# precharge.net
KiCad netlist of a schematic drawn in EAGLE
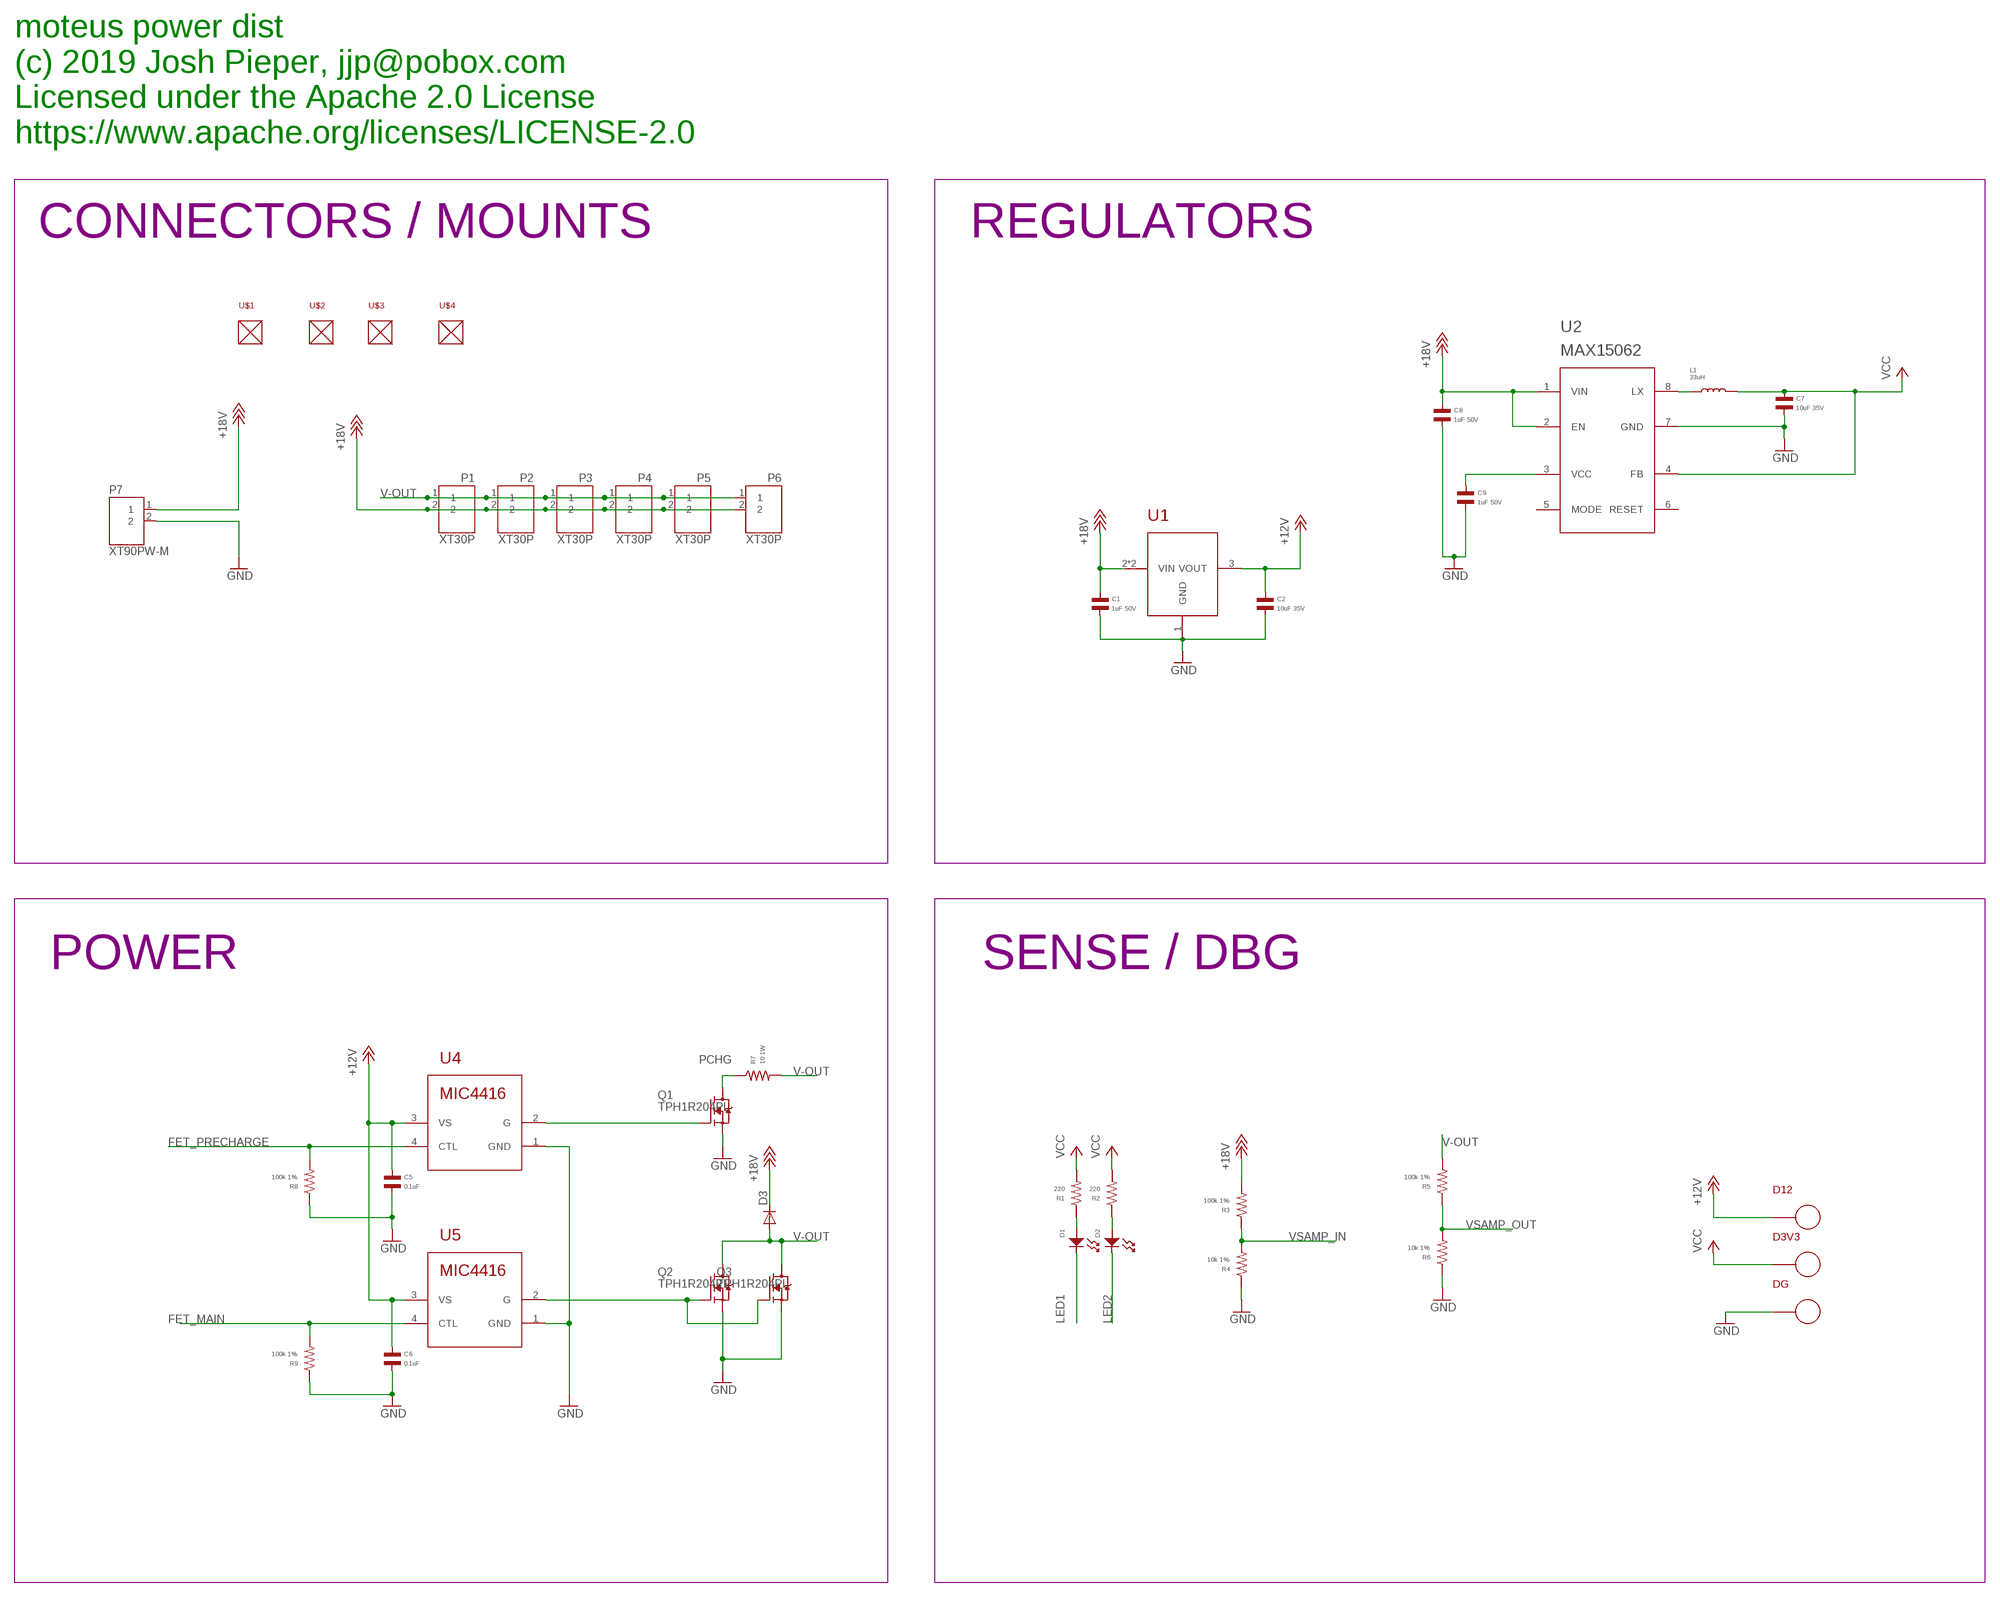
[diagram p0: schematic, sheet 1, part 1 of 2]
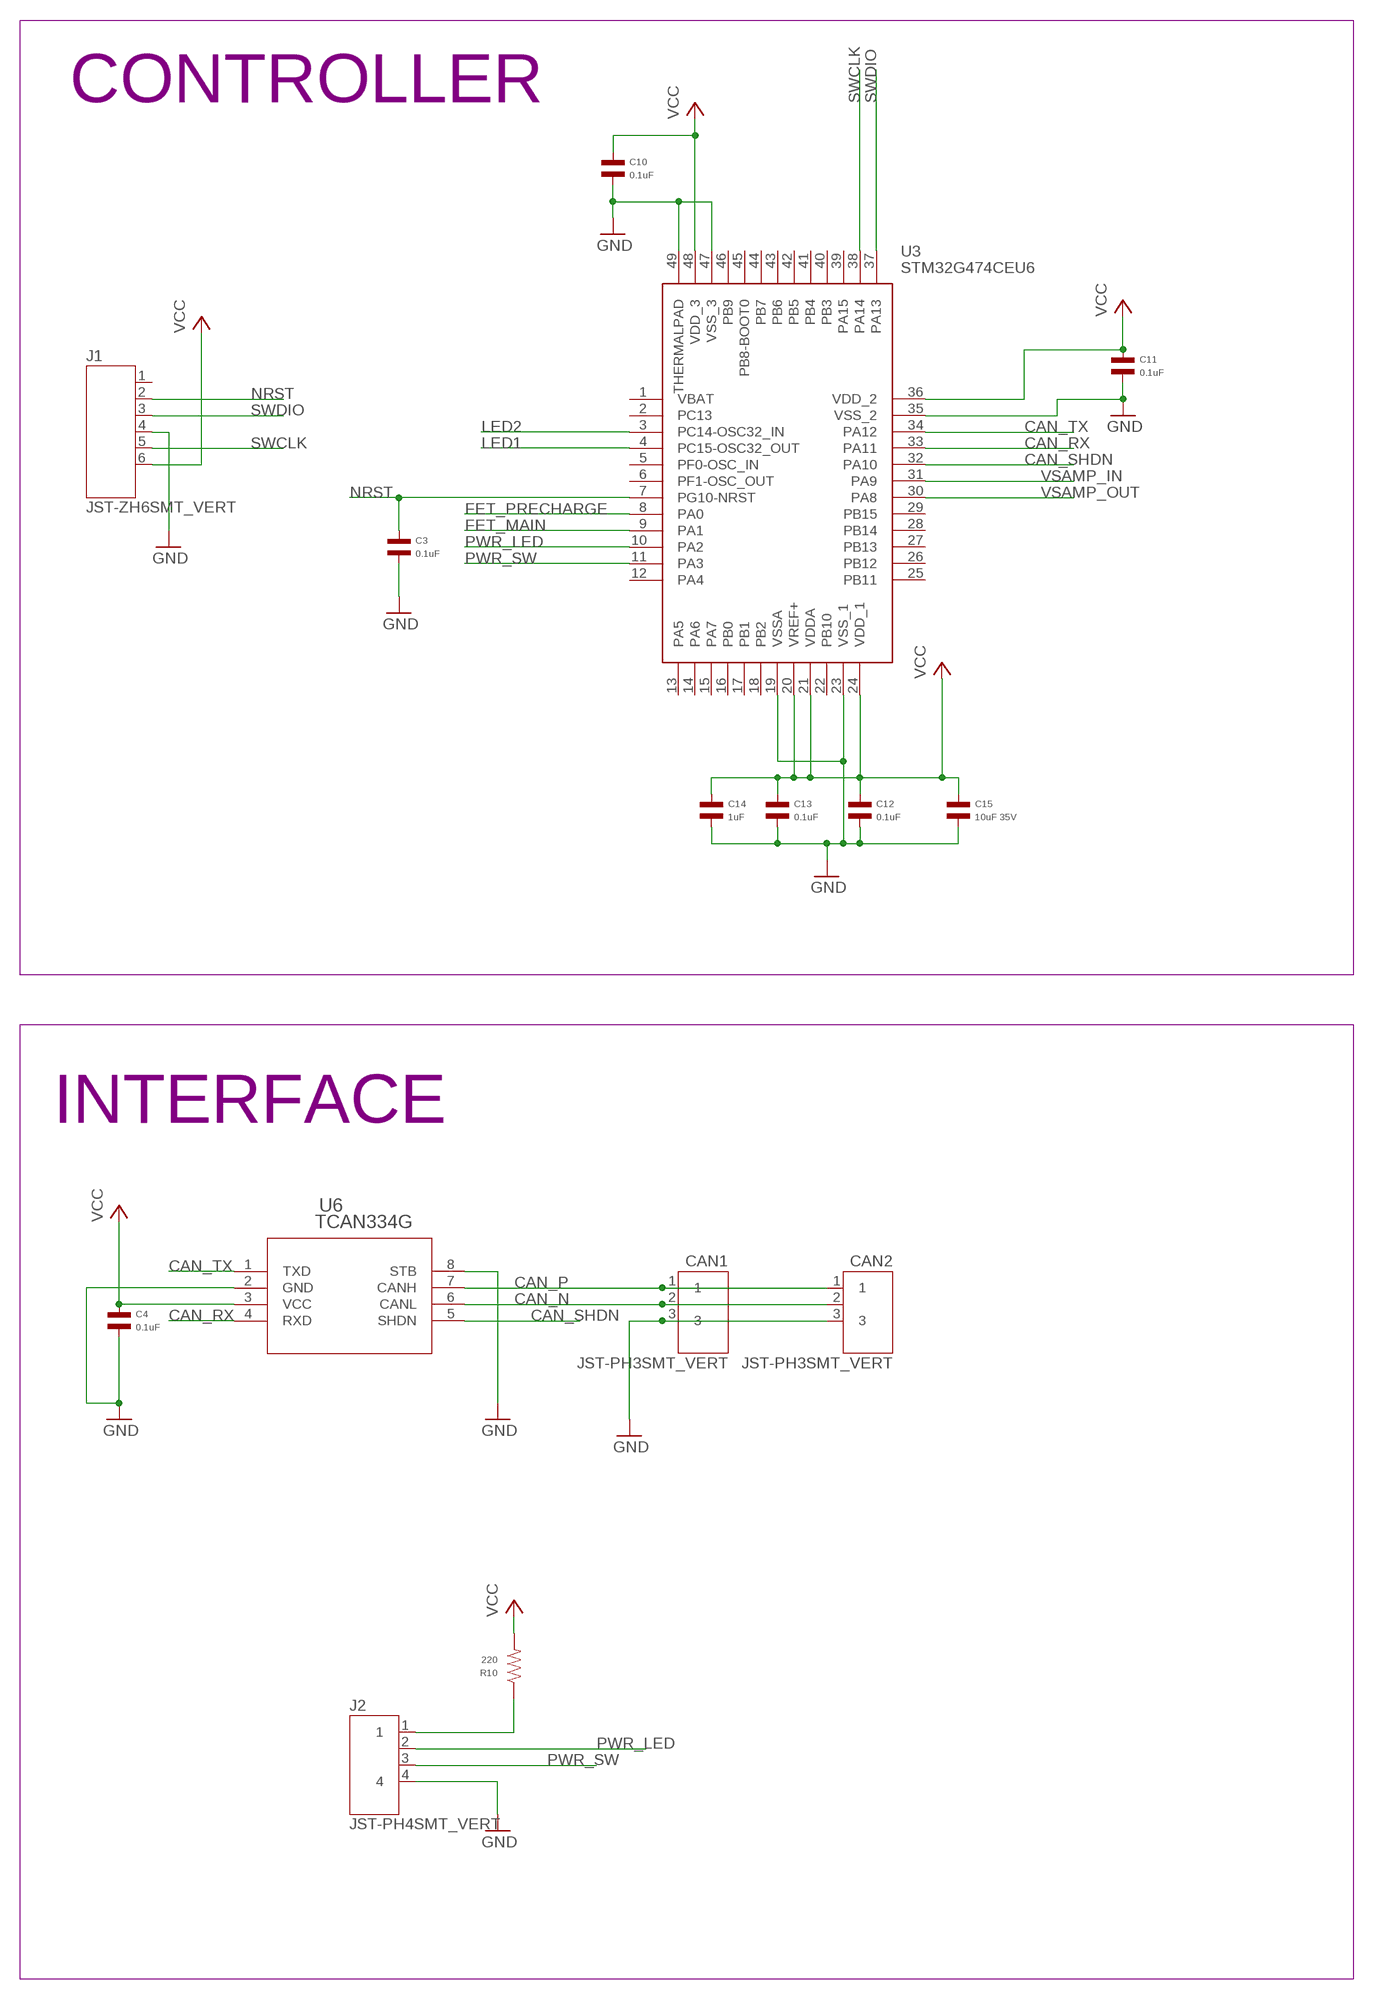
[diagram p1: schematic, sheet 1, part 2 of 2]

(export (version "E")
  (design (tool "Eeschema 10.0.6"))
  (components
    (comp (ref "C1")
      (value "1uF 50V")
      (footprint "eagle-import:C0603")
      (fields (field (name "MF") "SAMSUNG") (field (name "MPN") "CL10A105KB8NNNC"))
      (libsource (lib "eagle-import") (part "CAPACITOR_NP_0603"))
    )
    (comp (ref "C2")
      (value "10uF 35V")
      (footprint "eagle-import:C1206")
      (fields (field (name "MF") "TDK") (field (name "MPN") "CGA5L1X7R1V106K160AC"))
      (libsource (lib "eagle-import") (part "CAPACITOR_NP_1206"))
    )
    (comp (ref "C3")
      (value "0.1uF")
      (footprint "eagle-import:C0402")
      (fields (field (name "HOUSEPART") "1") (field (name "MPN") "MF-CAP-0402-0.1uF"))
      (libsource (lib "eagle-import") (part "CAPACITOR_NP_0402"))
    )
    (comp (ref "C4")
      (value "0.1uF")
      (footprint "eagle-import:C0402")
      (fields (field (name "HOUSEPART") "1") (field (name "MPN") "MF-CAP-0402-0.1uF"))
      (libsource (lib "eagle-import") (part "CAPACITOR_NP_0402"))
    )
    (comp (ref "C5")
      (value "0.1uF")
      (footprint "eagle-import:C0402")
      (fields (field (name "HOUSEPART") "1") (field (name "MPN") "MF-CAP-0402-0.1uF"))
      (libsource (lib "eagle-import") (part "CAPACITOR_NP_0402"))
    )
    (comp (ref "C6")
      (value "0.1uF")
      (footprint "eagle-import:C0402")
      (fields (field (name "HOUSEPART") "1") (field (name "MPN") "MF-CAP-0402-0.1uF"))
      (libsource (lib "eagle-import") (part "CAPACITOR_NP_0402"))
    )
    (comp (ref "C7")
      (value "10uF 35V")
      (footprint "eagle-import:C1206")
      (fields (field (name "MF") "TDK") (field (name "MPN") "CGA5L1X7R1V106K160AC"))
      (libsource (lib "eagle-import") (part "CAPACITOR_NP_1206"))
    )
    (comp (ref "C8")
      (value "1uF 50V")
      (footprint "eagle-import:C0603")
      (fields (field (name "MF") "SAMSUNG") (field (name "MPN") "CL10A105KB8NNNC"))
      (libsource (lib "eagle-import") (part "CAPACITOR_NP_0603"))
    )
    (comp (ref "C9")
      (value "1uF 50V")
      (footprint "eagle-import:C0603")
      (fields (field (name "MF") "SAMSUNG") (field (name "MPN") "CL10A105KB8NNNC"))
      (libsource (lib "eagle-import") (part "CAPACITOR_NP_0603"))
    )
    (comp (ref "C10")
      (value "0.1uF")
      (footprint "eagle-import:C0402")
      (fields (field (name "HOUSEPART") "1") (field (name "MPN") "MF-CAP-0402-0.1uF"))
      (libsource (lib "eagle-import") (part "CAPACITOR_NP_0402"))
    )
    (comp (ref "C11")
      (value "0.1uF")
      (footprint "eagle-import:C0402")
      (fields (field (name "HOUSEPART") "1") (field (name "MPN") "MF-CAP-0402-0.1uF"))
      (libsource (lib "eagle-import") (part "CAPACITOR_NP_0402"))
    )
    (comp (ref "C12")
      (value "0.1uF")
      (footprint "eagle-import:C0402")
      (fields (field (name "HOUSEPART") "1") (field (name "MPN") "MF-CAP-0402-0.1uF"))
      (libsource (lib "eagle-import") (part "CAPACITOR_NP_0402"))
    )
    (comp (ref "C13")
      (value "0.1uF")
      (footprint "eagle-import:C0402")
      (fields (field (name "HOUSEPART") "1") (field (name "MPN") "MF-CAP-0402-0.1uF"))
      (libsource (lib "eagle-import") (part "CAPACITOR_NP_0402"))
    )
    (comp (ref "C14")
      (value "1uF")
      (footprint "eagle-import:C0402")
      (fields (field (name "HOUSEPART") "1") (field (name "MPN") "MF-CAP-0402-1uF"))
      (libsource (lib "eagle-import") (part "CAPACITOR_NP_0402"))
    )
    (comp (ref "C15")
      (value "10uF 35V")
      (footprint "eagle-import:C1206")
      (fields (field (name "MF") "TDK") (field (name "MPN") "CGA5L1X7R1V106K160AC"))
      (libsource (lib "eagle-import") (part "CAPACITOR_NP_1206"))
    )
    (comp (ref "CAN1")
      (value "JST-PH3SMT_VERT")
      (footprint "eagle-import:JST_B3B_PH-SM4-TB(LF)(SN)")
      (fields (field (name "MF") "JST") (field (name "MPN") "B3B-PH-SM4-TB(LF)(SN)"))
      (libsource (lib "eagle-import") (part "JST-PH3SMT_VERT"))
    )
    (comp (ref "CAN2")
      (value "JST-PH3SMT_VERT")
      (footprint "eagle-import:JST_B3B_PH-SM4-TB(LF)(SN)")
      (fields (field (name "MF") "JST") (field (name "MPN") "B3B-PH-SM4-TB(LF)(SN)"))
      (libsource (lib "eagle-import") (part "JST-PH3SMT_VERT"))
    )
    (comp (ref "D1")
      (value "LED_SINGLE-0603")
      (footprint "eagle-import:LED0603")
      (fields
        (field (name "HOUSEPART") "NO")
        (field (name "HOUSEPART_1") "1")
        (field (name "MPN") "MF-LED-0603-RED")
      )
      (libsource (lib "eagle-import") (part "LED_SINGLE-0603"))
    )
    (comp (ref "D2")
      (value "LED_SINGLE-0603")
      (footprint "eagle-import:LED0603")
      (fields
        (field (name "HOUSEPART") "NO")
        (field (name "HOUSEPART_1") "1")
        (field (name "MPN") "MF-LED-0603-RED")
      )
      (libsource (lib "eagle-import") (part "LED_SINGLE-0603"))
    )
    (comp (ref "D3")
      (value "DIODE-")
      (footprint "eagle-import:DO-214AB")
      (fields (field (name "MF") "MICRO COMMERCIAL") (field (name "MPN") "SK510L-TP"))
      (libsource (lib "eagle-import") (part "DIODE-"))
    )
    (comp (ref "D3V3")
      (value "PAD24AWG_PAD")
      (footprint "eagle-import:24AWG_PAD")
      (libsource (lib "eagle-import") (part "PAD24AWG_PAD"))
    )
    (comp (ref "D12")
      (value "PAD24AWG_PAD")
      (footprint "eagle-import:24AWG_PAD")
      (libsource (lib "eagle-import") (part "PAD24AWG_PAD"))
    )
    (comp (ref "DG")
      (value "PAD24AWG_PAD")
      (footprint "eagle-import:24AWG_PAD")
      (libsource (lib "eagle-import") (part "PAD24AWG_PAD"))
    )
    (comp (ref "J1")
      (value "JST-ZH6SMT_VERT")
      (footprint "eagle-import:JST_B6B-ZR-SM4-TF(LF)(SN)")
      (fields (field (name "MF") "JST") (field (name "MPN") "B6B-ZR-SM4-TF(LF)(SN)"))
      (libsource (lib "eagle-import") (part "JST-ZH6SMT_VERT"))
    )
    (comp (ref "J2")
      (value "JST-PH4SMT_VERT")
      (footprint "eagle-import:JST_B4B_PH-SM4-TB(LF)(SN)")
      (fields (field (name "MF") "JST") (field (name "MPN") "B4B-PH-SM4-TB(LF)(SN)"))
      (libsource (lib "eagle-import") (part "JST-PH4SMT_VERT"))
    )
    (comp (ref "L1")
      (value "33uH")
      (footprint "eagle-import:L1210")
      (fields (field (name "MF") "TDK") (field (name "MPN") "NLFV32T-330K-EF") (field (name "POPULATE") "1"))
      (libsource (lib "eagle-import") (part "INDUCTOR_1210"))
    )
    (comp (ref "P1")
      (value "XT30P")
      (footprint "eagle-import:XT30P")
      (libsource (lib "eagle-import") (part "XT30P"))
    )
    (comp (ref "P2")
      (value "XT30P")
      (footprint "eagle-import:XT30P")
      (libsource (lib "eagle-import") (part "XT30P"))
    )
    (comp (ref "P3")
      (value "XT30P")
      (footprint "eagle-import:XT30P")
      (libsource (lib "eagle-import") (part "XT30P"))
    )
    (comp (ref "P4")
      (value "XT30P")
      (footprint "eagle-import:XT30P")
      (libsource (lib "eagle-import") (part "XT30P"))
    )
    (comp (ref "P5")
      (value "XT30P")
      (footprint "eagle-import:XT30P")
      (libsource (lib "eagle-import") (part "XT30P"))
    )
    (comp (ref "P6")
      (value "XT30P")
      (footprint "eagle-import:XT30P")
      (libsource (lib "eagle-import") (part "XT30P"))
    )
    (comp (ref "P7")
      (value "XT90PW-M")
      (footprint "eagle-import:XT90PW-M")
      (libsource (lib "eagle-import") (part "XT90PW-M"))
    )
    (comp (ref "Q1")
      (value "TPH1R204PL")
      (footprint "eagle-import:SOP_ADVANCE")
      (fields (field (name "MF") "Toshiba") (field (name "MPN") "TPH1R204PL,L1Q"))
      (libsource (lib "eagle-import") (part "TPH1R204PL"))
    )
    (comp (ref "Q2")
      (value "TPH1R204PL")
      (footprint "eagle-import:SOP_ADVANCE")
      (fields (field (name "MF") "Toshiba") (field (name "MPN") "TPH1R204PL,L1Q"))
      (libsource (lib "eagle-import") (part "TPH1R204PL"))
    )
    (comp (ref "Q3")
      (value "TPH1R204PL")
      (footprint "eagle-import:SOP_ADVANCE")
      (fields (field (name "MF") "Toshiba") (field (name "MPN") "TPH1R204PL,L1Q"))
      (libsource (lib "eagle-import") (part "TPH1R204PL"))
    )
    (comp (ref "R1")
      (value "220")
      (footprint "eagle-import:R0603")
      (fields (field (name "HOUSEPART") "1") (field (name "MPN") "MF-RES-0603-220"))
      (libsource (lib "eagle-import") (part "RESISTOR_0603"))
    )
    (comp (ref "R2")
      (value "220")
      (footprint "eagle-import:R0603")
      (fields (field (name "HOUSEPART") "1") (field (name "MPN") "MF-RES-0603-220"))
      (libsource (lib "eagle-import") (part "RESISTOR_0603"))
    )
    (comp (ref "R3")
      (value "100k 1%")
      (footprint "eagle-import:R0603")
      (fields (field (name "MF") "VISHAY") (field (name "MPN") "CRCW0603100KFKEA"))
      (libsource (lib "eagle-import") (part "RESISTOR_0603"))
    )
    (comp (ref "R4")
      (value "10k 1%")
      (footprint "eagle-import:R0603")
      (fields (field (name "MF") "PANASONIC") (field (name "MPN") "ERT-J1VG103FA"))
      (libsource (lib "eagle-import") (part "RESISTOR_0603"))
    )
    (comp (ref "R5")
      (value "100k 1%")
      (footprint "eagle-import:R0603")
      (fields (field (name "MF") "VISHAY") (field (name "MPN") "CRCW0603100KFKEA"))
      (libsource (lib "eagle-import") (part "RESISTOR_0603"))
    )
    (comp (ref "R6")
      (value "10k 1%")
      (footprint "eagle-import:R0603")
      (fields (field (name "MF") "PANASONIC") (field (name "MPN") "ERT-J1VG103FA"))
      (libsource (lib "eagle-import") (part "RESISTOR_0603"))
    )
    (comp (ref "R7")
      (value "10 1W")
      (footprint "eagle-import:R1206")
      (fields (field (name "MF") "Susumu") (field (name "MPN") "HRG3216Q-10R0-D-T1"))
      (libsource (lib "eagle-import") (part "RESISTOR_1206"))
    )
    (comp (ref "R8")
      (value "100k 1%")
      (footprint "eagle-import:R0603")
      (fields (field (name "MF") "VISHAY") (field (name "MPN") "CRCW0603100KFKEA"))
      (libsource (lib "eagle-import") (part "RESISTOR_0603"))
    )
    (comp (ref "R9")
      (value "100k 1%")
      (footprint "eagle-import:R0603")
      (fields (field (name "MF") "VISHAY") (field (name "MPN") "CRCW0603100KFKEA"))
      (libsource (lib "eagle-import") (part "RESISTOR_0603"))
    )
    (comp (ref "R10")
      (value "220")
      (footprint "eagle-import:R0603")
      (fields (field (name "HOUSEPART") "1") (field (name "MPN") "MF-RES-0603-220"))
      (libsource (lib "eagle-import") (part "RESISTOR_0603"))
    )
    (comp (ref "U$1")
      (value "MOUNT")
      (footprint "eagle-import:M2.5MOUNT")
      (libsource (lib "eagle-import") (part "MOUNT"))
    )
    (comp (ref "U$2")
      (value "MOUNT")
      (footprint "eagle-import:M2.5MOUNT")
      (libsource (lib "eagle-import") (part "MOUNT"))
    )
    (comp (ref "U$3")
      (value "MOUNT")
      (footprint "eagle-import:M2.5MOUNT")
      (libsource (lib "eagle-import") (part "MOUNT"))
    )
    (comp (ref "U$4")
      (value "MOUNT")
      (footprint "eagle-import:M2.5MOUNT")
      (libsource (lib "eagle-import") (part "MOUNT"))
    )
    (comp (ref "U1")
      (value "ZXTR2012Z")
      (footprint "eagle-import:SOT89")
      (fields (field (name "MF") "DIODES INC") (field (name "MPN") "ZXTR2012Z-13"))
      (libsource (lib "eagle-import") (part "ZXTR2012Z"))
    )
    (comp (ref "U2")
      (value "MAX150628TDFN")
      (footprint "eagle-import:8TDFN")
      (fields (field (name "MF") "MAXIM") (field (name "MPN") "MAX15062AATA+T"))
      (libsource (lib "eagle-import") (part "MAX150628TDFN"))
    )
    (comp (ref "U3")
      (value "STM32G474CEU6")
      (footprint "eagle-import:QFN50P700X700X60-49N")
      (fields (field (name "MOUSER_PART_NUMBER") "511-STM32G474CEU6") (field (name "MF") "ST"))
      (libsource (lib "eagle-import") (part "STM32G474CEU6"))
    )
    (comp (ref "U4")
      (value "MIC4416")
      (footprint "eagle-import:SOT143")
      (fields (field (name "MF") "MICROCHIP") (field (name "MPN") "MIC4416YM4-TR"))
      (libsource (lib "eagle-import") (part "MIC4416"))
    )
    (comp (ref "U5")
      (value "MIC4416")
      (footprint "eagle-import:SOT143")
      (fields (field (name "MF") "MICROCHIP") (field (name "MPN") "MIC4416YM4-TR"))
      (libsource (lib "eagle-import") (part "MIC4416"))
    )
    (comp (ref "U6")
      (value "TCAN334G")
      (footprint "eagle-import:SOT23-8")
      (fields (field (name "MF") "TI") (field (name "MPN") "TCAN334GDR"))
      (libsource (lib "eagle-import") (part "TCAN334G"))
    )
  )
  (nets
    (net (code "1") (name "+12V") (class "Default")
      (node (ref "C2") (pin "P$1") (pinfunction "P$1_P$1") (pintype "passive"))
      (node (ref "C5") (pin "P$1") (pinfunction "P$1_P$1") (pintype "passive"))
      (node (ref "C6") (pin "P$1") (pinfunction "P$1_P$1") (pintype "passive"))
      (node (ref "D12") (pin "P$1") (pinfunction "P$1_P$1") (pintype "bidirectional"))
      (node (ref "U1") (pin "3") (pinfunction "VOUT_3") (pintype "bidirectional"))
      (node (ref "U4") (pin "3") (pinfunction "VS_3") (pintype "bidirectional"))
      (node (ref "U5") (pin "3") (pinfunction "VS_3") (pintype "bidirectional"))
    )
    (net (code "2") (name "+18V") (class "Default")
      (node (ref "C1") (pin "P$1") (pinfunction "P$1_P$1") (pintype "passive"))
      (node (ref "C8") (pin "P$1") (pinfunction "P$1_P$1") (pintype "passive"))
      (node (ref "D3") (pin "C") (pinfunction "C_C") (pintype "passive"))
      (node (ref "P1") (pin "2") (pinfunction "2_2") (pintype "passive"))
      (node (ref "P2") (pin "2") (pinfunction "2_2") (pintype "passive"))
      (node (ref "P3") (pin "2") (pinfunction "2_2") (pintype "passive"))
      (node (ref "P4") (pin "2") (pinfunction "2_2") (pintype "passive"))
      (node (ref "P5") (pin "2") (pinfunction "2_2") (pintype "passive"))
      (node (ref "P6") (pin "2") (pinfunction "2_2") (pintype "passive"))
      (node (ref "P7") (pin "1") (pinfunction "1_1") (pintype "passive"))
      (node (ref "R3") (pin "P$2") (pinfunction "P$2_P$2") (pintype "passive"))
      (node (ref "U1") (pin "2") (pinfunction "VIN_2") (pintype "bidirectional"))
      (node (ref "U1") (pin "PAD") (pinfunction "VIN_PAD") (pintype "bidirectional"))
      (node (ref "U2") (pin "1") (pinfunction "VIN_1") (pintype "passive"))
      (node (ref "U2") (pin "2") (pinfunction "EN_2") (pintype "passive"))
    )
    (net (code "3") (name "/CAN_N") (class "Default")
      (node (ref "CAN1") (pin "2") (pinfunction "2_2") (pintype "passive"))
      (node (ref "CAN2") (pin "2") (pinfunction "2_2") (pintype "passive"))
      (node (ref "U6") (pin "6") (pinfunction "CANL_6") (pintype "bidirectional"))
    )
    (net (code "4") (name "/CAN_P") (class "Default")
      (node (ref "CAN1") (pin "1") (pinfunction "1_1") (pintype "passive"))
      (node (ref "CAN2") (pin "1") (pinfunction "1_1") (pintype "passive"))
      (node (ref "U6") (pin "7") (pinfunction "CANH_7") (pintype "bidirectional"))
    )
    (net (code "5") (name "/CAN_RX") (class "Default")
      (node (ref "U3") (pin "33") (pinfunction "PA11_33") (pintype "bidirectional"))
      (node (ref "U6") (pin "4") (pinfunction "RXD_4") (pintype "output"))
    )
    (net (code "6") (name "/CAN_SHDN") (class "Default")
      (node (ref "U3") (pin "32") (pinfunction "PA10_32") (pintype "bidirectional"))
      (node (ref "U6") (pin "5") (pinfunction "SHDN_5") (pintype "input"))
    )
    (net (code "7") (name "/CAN_TX") (class "Default")
      (node (ref "U3") (pin "34") (pinfunction "PA12_34") (pintype "bidirectional"))
      (node (ref "U6") (pin "1") (pinfunction "TXD_1") (pintype "input"))
    )
    (net (code "8") (name "/FET_MAIN") (class "Default")
      (node (ref "R9") (pin "P$2") (pinfunction "P$2_P$2") (pintype "passive"))
      (node (ref "U3") (pin "9") (pinfunction "PA1_9") (pintype "bidirectional"))
      (node (ref "U5") (pin "4") (pinfunction "CTL_4") (pintype "bidirectional"))
    )
    (net (code "9") (name "/FET_PRECHARGE") (class "Default")
      (node (ref "R8") (pin "P$2") (pinfunction "P$2_P$2") (pintype "passive"))
      (node (ref "U3") (pin "8") (pinfunction "PA0_8") (pintype "bidirectional"))
      (node (ref "U4") (pin "4") (pinfunction "CTL_4") (pintype "bidirectional"))
    )
    (net (code "10") (name "/LED1") (class "Default")
      (node (ref "D1") (pin "CATHODE") (pinfunction "CATHODE_CATHODE") (pintype "power_in"))
      (node (ref "U3") (pin "4") (pinfunction "PC15-OSC32_OUT_4") (pintype "bidirectional"))
    )
    (net (code "11") (name "/LED2") (class "Default")
      (node (ref "D2") (pin "CATHODE") (pinfunction "CATHODE_CATHODE") (pintype "power_in"))
      (node (ref "U3") (pin "3") (pinfunction "PC14-OSC32_IN_3") (pintype "bidirectional"))
    )
    (net (code "12") (name "/NRST") (class "Default")
      (node (ref "C3") (pin "P$1") (pinfunction "P$1_P$1") (pintype "passive"))
      (node (ref "J1") (pin "2") (pinfunction "2_2") (pintype "passive"))
      (node (ref "U3") (pin "7") (pinfunction "PG10-NRST_7") (pintype "bidirectional"))
    )
    (net (code "13") (name "/PCHG") (class "Default")
      (node (ref "Q1") (pin "5") (pinfunction "D_5") (pintype "passive"))
      (node (ref "Q1") (pin "6") (pinfunction "D_6") (pintype "passive"))
      (node (ref "Q1") (pin "7") (pinfunction "D_7") (pintype "passive"))
      (node (ref "Q1") (pin "8") (pinfunction "D_8") (pintype "passive"))
      (node (ref "Q1") (pin "PAD") (pinfunction "D_PAD") (pintype "passive"))
      (node (ref "R7") (pin "P$1") (pinfunction "P$1_P$1") (pintype "passive"))
    )
    (net (code "14") (name "/PWR_LED") (class "Default")
      (node (ref "J2") (pin "2") (pinfunction "2_2") (pintype "passive"))
      (node (ref "U3") (pin "10") (pinfunction "PA2_10") (pintype "bidirectional"))
    )
    (net (code "15") (name "/PWR_SW") (class "Default")
      (node (ref "J2") (pin "3") (pinfunction "3_3") (pintype "passive"))
      (node (ref "U3") (pin "11") (pinfunction "PA3_11") (pintype "bidirectional"))
    )
    (net (code "16") (name "/SWCLK") (class "Default")
      (node (ref "J1") (pin "5") (pinfunction "5_5") (pintype "passive"))
      (node (ref "U3") (pin "38") (pinfunction "PA14_38") (pintype "bidirectional"))
    )
    (net (code "17") (name "/SWDIO") (class "Default")
      (node (ref "J1") (pin "3") (pinfunction "3_3") (pintype "passive"))
      (node (ref "U3") (pin "37") (pinfunction "PA13_37") (pintype "bidirectional"))
    )
    (net (code "18") (name "/V-OUT") (class "Default")
      (node (ref "D3") (pin "A") (pinfunction "A_A") (pintype "passive"))
      (node (ref "P1") (pin "1") (pinfunction "1_1") (pintype "passive"))
      (node (ref "P2") (pin "1") (pinfunction "1_1") (pintype "passive"))
      (node (ref "P3") (pin "1") (pinfunction "1_1") (pintype "passive"))
      (node (ref "P4") (pin "1") (pinfunction "1_1") (pintype "passive"))
      (node (ref "P5") (pin "1") (pinfunction "1_1") (pintype "passive"))
      (node (ref "P6") (pin "1") (pinfunction "1_1") (pintype "passive"))
      (node (ref "Q2") (pin "5") (pinfunction "D_5") (pintype "passive"))
      (node (ref "Q2") (pin "6") (pinfunction "D_6") (pintype "passive"))
      (node (ref "Q2") (pin "7") (pinfunction "D_7") (pintype "passive"))
      (node (ref "Q2") (pin "8") (pinfunction "D_8") (pintype "passive"))
      (node (ref "Q2") (pin "PAD") (pinfunction "D_PAD") (pintype "passive"))
      (node (ref "Q3") (pin "5") (pinfunction "D_5") (pintype "passive"))
      (node (ref "Q3") (pin "6") (pinfunction "D_6") (pintype "passive"))
      (node (ref "Q3") (pin "7") (pinfunction "D_7") (pintype "passive"))
      (node (ref "Q3") (pin "8") (pinfunction "D_8") (pintype "passive"))
      (node (ref "Q3") (pin "PAD") (pinfunction "D_PAD") (pintype "passive"))
      (node (ref "R5") (pin "P$2") (pinfunction "P$2_P$2") (pintype "passive"))
      (node (ref "R7") (pin "P$2") (pinfunction "P$2_P$2") (pintype "passive"))
    )
    (net (code "19") (name "/VSAMP_IN") (class "Default")
      (node (ref "R3") (pin "P$1") (pinfunction "P$1_P$1") (pintype "passive"))
      (node (ref "R4") (pin "P$2") (pinfunction "P$2_P$2") (pintype "passive"))
      (node (ref "U3") (pin "31") (pinfunction "PA9_31") (pintype "bidirectional"))
    )
    (net (code "20") (name "/VSAMP_OUT") (class "Default")
      (node (ref "R5") (pin "P$1") (pinfunction "P$1_P$1") (pintype "passive"))
      (node (ref "R6") (pin "P$2") (pinfunction "P$2_P$2") (pintype "passive"))
      (node (ref "U3") (pin "30") (pinfunction "PA8_30") (pintype "bidirectional"))
    )
    (net (code "21") (name "GND") (class "Default")
      (node (ref "C1") (pin "P$2") (pinfunction "P$2_P$2") (pintype "passive"))
      (node (ref "C10") (pin "P$2") (pinfunction "P$2_P$2") (pintype "passive"))
      (node (ref "C11") (pin "P$2") (pinfunction "P$2_P$2") (pintype "passive"))
      (node (ref "C12") (pin "P$2") (pinfunction "P$2_P$2") (pintype "passive"))
      (node (ref "C13") (pin "P$2") (pinfunction "P$2_P$2") (pintype "passive"))
      (node (ref "C14") (pin "P$2") (pinfunction "P$2_P$2") (pintype "passive"))
      (node (ref "C15") (pin "P$2") (pinfunction "P$2_P$2") (pintype "passive"))
      (node (ref "C2") (pin "P$2") (pinfunction "P$2_P$2") (pintype "passive"))
      (node (ref "C3") (pin "P$2") (pinfunction "P$2_P$2") (pintype "passive"))
      (node (ref "C4") (pin "P$2") (pinfunction "P$2_P$2") (pintype "passive"))
      (node (ref "C5") (pin "P$2") (pinfunction "P$2_P$2") (pintype "passive"))
      (node (ref "C6") (pin "P$2") (pinfunction "P$2_P$2") (pintype "passive"))
      (node (ref "C7") (pin "P$2") (pinfunction "P$2_P$2") (pintype "passive"))
      (node (ref "C8") (pin "P$2") (pinfunction "P$2_P$2") (pintype "passive"))
      (node (ref "C9") (pin "P$2") (pinfunction "P$2_P$2") (pintype "passive"))
      (node (ref "CAN1") (pin "3") (pinfunction "3_3") (pintype "passive"))
      (node (ref "CAN2") (pin "3") (pinfunction "3_3") (pintype "passive"))
      (node (ref "DG") (pin "P$1") (pinfunction "P$1_P$1") (pintype "bidirectional"))
      (node (ref "J1") (pin "4") (pinfunction "4_4") (pintype "passive"))
      (node (ref "J2") (pin "4") (pinfunction "4_4") (pintype "passive"))
      (node (ref "P7") (pin "2") (pinfunction "2_2") (pintype "passive"))
      (node (ref "Q1") (pin "1") (pinfunction "S_1") (pintype "passive"))
      (node (ref "Q1") (pin "2") (pinfunction "S_2") (pintype "passive"))
      (node (ref "Q1") (pin "3") (pinfunction "S_3") (pintype "passive"))
      (node (ref "Q2") (pin "1") (pinfunction "S_1") (pintype "passive"))
      (node (ref "Q2") (pin "2") (pinfunction "S_2") (pintype "passive"))
      (node (ref "Q2") (pin "3") (pinfunction "S_3") (pintype "passive"))
      (node (ref "Q3") (pin "1") (pinfunction "S_1") (pintype "passive"))
      (node (ref "Q3") (pin "2") (pinfunction "S_2") (pintype "passive"))
      (node (ref "Q3") (pin "3") (pinfunction "S_3") (pintype "passive"))
      (node (ref "R4") (pin "P$1") (pinfunction "P$1_P$1") (pintype "passive"))
      (node (ref "R6") (pin "P$1") (pinfunction "P$1_P$1") (pintype "passive"))
      (node (ref "R8") (pin "P$1") (pinfunction "P$1_P$1") (pintype "passive"))
      (node (ref "R9") (pin "P$1") (pinfunction "P$1_P$1") (pintype "passive"))
      (node (ref "U1") (pin "1") (pinfunction "GND_1") (pintype "bidirectional"))
      (node (ref "U2") (pin "7") (pinfunction "GND_7") (pintype "passive"))
      (node (ref "U3") (pin "19") (pinfunction "VSSA_19") (pintype "bidirectional"))
      (node (ref "U3") (pin "23") (pinfunction "VSS_1_23") (pintype "bidirectional"))
      (node (ref "U3") (pin "35") (pinfunction "VSS_2_35") (pintype "bidirectional"))
      (node (ref "U3") (pin "47") (pinfunction "VSS_3_47") (pintype "bidirectional"))
      (node (ref "U3") (pin "49") (pinfunction "THERMALPAD_49") (pintype "bidirectional"))
      (node (ref "U4") (pin "1") (pinfunction "GND_1") (pintype "bidirectional"))
      (node (ref "U5") (pin "1") (pinfunction "GND_1") (pintype "bidirectional"))
      (node (ref "U6") (pin "2") (pinfunction "GND_2") (pintype "power_in"))
      (node (ref "U6") (pin "8") (pinfunction "STB_8") (pintype "input"))
    )
    (net (code "22") (name "Net-(D1-PadANODE)") (class "Default")
      (node (ref "D1") (pin "ANODE") (pinfunction "ANODE_ANODE") (pintype "power_in"))
      (node (ref "R1") (pin "P$1") (pinfunction "P$1_P$1") (pintype "passive"))
    )
    (net (code "23") (name "Net-(D2-PadANODE)") (class "Default")
      (node (ref "D2") (pin "ANODE") (pinfunction "ANODE_ANODE") (pintype "power_in"))
      (node (ref "R2") (pin "P$1") (pinfunction "P$1_P$1") (pintype "passive"))
    )
    (net (code "24") (name "Net-(J2-Pad1)") (class "Default")
      (node (ref "J2") (pin "1") (pinfunction "1_1") (pintype "passive"))
      (node (ref "R10") (pin "P$1") (pinfunction "P$1_P$1") (pintype "passive"))
    )
    (net (code "25") (name "Net-(Q1-G)") (class "Default")
      (node (ref "Q1") (pin "4") (pinfunction "G_4") (pintype "passive"))
      (node (ref "U4") (pin "2") (pinfunction "G_2") (pintype "bidirectional"))
    )
    (net (code "26") (name "Net-(Q2-G)") (class "Default")
      (node (ref "Q2") (pin "4") (pinfunction "G_4") (pintype "passive"))
      (node (ref "Q3") (pin "4") (pinfunction "G_4") (pintype "passive"))
      (node (ref "U5") (pin "2") (pinfunction "G_2") (pintype "bidirectional"))
    )
    (net (code "27") (name "Net-(U2-LX)") (class "Default")
      (node (ref "L1") (pin "P$1") (pinfunction "P$1_P$1") (pintype "passive"))
      (node (ref "U2") (pin "8") (pinfunction "LX_8") (pintype "passive"))
    )
    (net (code "28") (name "Net-(U2-VCC)") (class "Default")
      (node (ref "C9") (pin "P$1") (pinfunction "P$1_P$1") (pintype "passive"))
      (node (ref "U2") (pin "3") (pinfunction "VCC_3") (pintype "passive"))
    )
    (net (code "29") (name "VCC") (class "Default")
      (node (ref "C10") (pin "P$1") (pinfunction "P$1_P$1") (pintype "passive"))
      (node (ref "C11") (pin "P$1") (pinfunction "P$1_P$1") (pintype "passive"))
      (node (ref "C12") (pin "P$1") (pinfunction "P$1_P$1") (pintype "passive"))
      (node (ref "C13") (pin "P$1") (pinfunction "P$1_P$1") (pintype "passive"))
      (node (ref "C14") (pin "P$1") (pinfunction "P$1_P$1") (pintype "passive"))
      (node (ref "C15") (pin "P$1") (pinfunction "P$1_P$1") (pintype "passive"))
      (node (ref "C4") (pin "P$1") (pinfunction "P$1_P$1") (pintype "passive"))
      (node (ref "C7") (pin "P$1") (pinfunction "P$1_P$1") (pintype "passive"))
      (node (ref "D3V3") (pin "P$1") (pinfunction "P$1_P$1") (pintype "bidirectional"))
      (node (ref "J1") (pin "6") (pinfunction "6_6") (pintype "passive"))
      (node (ref "L1") (pin "P$2") (pinfunction "P$2_P$2") (pintype "passive"))
      (node (ref "R1") (pin "P$2") (pinfunction "P$2_P$2") (pintype "passive"))
      (node (ref "R10") (pin "P$2") (pinfunction "P$2_P$2") (pintype "passive"))
      (node (ref "R2") (pin "P$2") (pinfunction "P$2_P$2") (pintype "passive"))
      (node (ref "U2") (pin "4") (pinfunction "FB_4") (pintype "passive"))
      (node (ref "U3") (pin "20") (pinfunction "VREF+_20") (pintype "bidirectional"))
      (node (ref "U3") (pin "21") (pinfunction "VDDA_21") (pintype "bidirectional"))
      (node (ref "U3") (pin "24") (pinfunction "VDD_1_24") (pintype "bidirectional"))
      (node (ref "U3") (pin "36") (pinfunction "VDD_2_36") (pintype "bidirectional"))
      (node (ref "U3") (pin "48") (pinfunction "VDD_3_48") (pintype "bidirectional"))
      (node (ref "U6") (pin "3") (pinfunction "VCC_3") (pintype "power_in"))
    )
    (net (code "30") (name "unconnected-(J1-Pad1)") (class "Default")
      (node (ref "J1") (pin "1") (pinfunction "1_1") (pintype "passive"))
    )
    (net (code "31") (name "unconnected-(U2-MODE-Pad5)") (class "Default")
      (node (ref "U2") (pin "5") (pinfunction "MODE_5") (pintype "passive"))
    )
    (net (code "32") (name "unconnected-(U2-RESET-Pad6)") (class "Default")
      (node (ref "U2") (pin "6") (pinfunction "RESET_6") (pintype "passive"))
    )
    (net (code "33") (name "unconnected-(U3-PA4-Pad12)") (class "Default")
      (node (ref "U3") (pin "12") (pinfunction "PA4_12") (pintype "bidirectional"))
    )
    (net (code "34") (name "unconnected-(U3-PA5-Pad13)") (class "Default")
      (node (ref "U3") (pin "13") (pinfunction "PA5_13") (pintype "bidirectional"))
    )
    (net (code "35") (name "unconnected-(U3-PA6-Pad14)") (class "Default")
      (node (ref "U3") (pin "14") (pinfunction "PA6_14") (pintype "bidirectional"))
    )
    (net (code "36") (name "unconnected-(U3-PA7-Pad15)") (class "Default")
      (node (ref "U3") (pin "15") (pinfunction "PA7_15") (pintype "bidirectional"))
    )
    (net (code "37") (name "unconnected-(U3-PA15-Pad39)") (class "Default")
      (node (ref "U3") (pin "39") (pinfunction "PA15_39") (pintype "bidirectional"))
    )
    (net (code "38") (name "unconnected-(U3-PB0-Pad16)") (class "Default")
      (node (ref "U3") (pin "16") (pinfunction "PB0_16") (pintype "bidirectional"))
    )
    (net (code "39") (name "unconnected-(U3-PB1-Pad17)") (class "Default")
      (node (ref "U3") (pin "17") (pinfunction "PB1_17") (pintype "bidirectional"))
    )
    (net (code "40") (name "unconnected-(U3-PB2-Pad18)") (class "Default")
      (node (ref "U3") (pin "18") (pinfunction "PB2_18") (pintype "bidirectional"))
    )
    (net (code "41") (name "unconnected-(U3-PB3-Pad40)") (class "Default")
      (node (ref "U3") (pin "40") (pinfunction "PB3_40") (pintype "bidirectional"))
    )
    (net (code "42") (name "unconnected-(U3-PB4-Pad41)") (class "Default")
      (node (ref "U3") (pin "41") (pinfunction "PB4_41") (pintype "bidirectional"))
    )
    (net (code "43") (name "unconnected-(U3-PB5-Pad42)") (class "Default")
      (node (ref "U3") (pin "42") (pinfunction "PB5_42") (pintype "bidirectional"))
    )
    (net (code "44") (name "unconnected-(U3-PB6-Pad43)") (class "Default")
      (node (ref "U3") (pin "43") (pinfunction "PB6_43") (pintype "bidirectional"))
    )
    (net (code "45") (name "unconnected-(U3-PB7-Pad44)") (class "Default")
      (node (ref "U3") (pin "44") (pinfunction "PB7_44") (pintype "bidirectional"))
    )
    (net (code "46") (name "unconnected-(U3-PB8-BOOT0-Pad45)") (class "Default")
      (node (ref "U3") (pin "45") (pinfunction "PB8-BOOT0_45") (pintype "bidirectional"))
    )
    (net (code "47") (name "unconnected-(U3-PB9-Pad46)") (class "Default")
      (node (ref "U3") (pin "46") (pinfunction "PB9_46") (pintype "bidirectional"))
    )
    (net (code "48") (name "unconnected-(U3-PB10-Pad22)") (class "Default")
      (node (ref "U3") (pin "22") (pinfunction "PB10_22") (pintype "bidirectional"))
    )
    (net (code "49") (name "unconnected-(U3-PB11-Pad25)") (class "Default")
      (node (ref "U3") (pin "25") (pinfunction "PB11_25") (pintype "bidirectional"))
    )
    (net (code "50") (name "unconnected-(U3-PB12-Pad26)") (class "Default")
      (node (ref "U3") (pin "26") (pinfunction "PB12_26") (pintype "bidirectional"))
    )
    (net (code "51") (name "unconnected-(U3-PB13-Pad27)") (class "Default")
      (node (ref "U3") (pin "27") (pinfunction "PB13_27") (pintype "bidirectional"))
    )
    (net (code "52") (name "unconnected-(U3-PB14-Pad28)") (class "Default")
      (node (ref "U3") (pin "28") (pinfunction "PB14_28") (pintype "bidirectional"))
    )
    (net (code "53") (name "unconnected-(U3-PB15-Pad29)") (class "Default")
      (node (ref "U3") (pin "29") (pinfunction "PB15_29") (pintype "bidirectional"))
    )
    (net (code "54") (name "unconnected-(U3-PC13-Pad2)") (class "Default")
      (node (ref "U3") (pin "2") (pinfunction "PC13_2") (pintype "bidirectional"))
    )
    (net (code "55") (name "unconnected-(U3-PF0-OSC_IN-Pad5)") (class "Default")
      (node (ref "U3") (pin "5") (pinfunction "PF0-OSC_IN_5") (pintype "bidirectional"))
    )
    (net (code "56") (name "unconnected-(U3-PF1-OSC_OUT-Pad6)") (class "Default")
      (node (ref "U3") (pin "6") (pinfunction "PF1-OSC_OUT_6") (pintype "bidirectional"))
    )
    (net (code "57") (name "unconnected-(U3-VBAT-Pad1)") (class "Default")
      (node (ref "U3") (pin "1") (pinfunction "VBAT_1") (pintype "bidirectional"))
    )
  )
)
